# power.net
KiCad netlist of a schematic drawn in Altium Designer
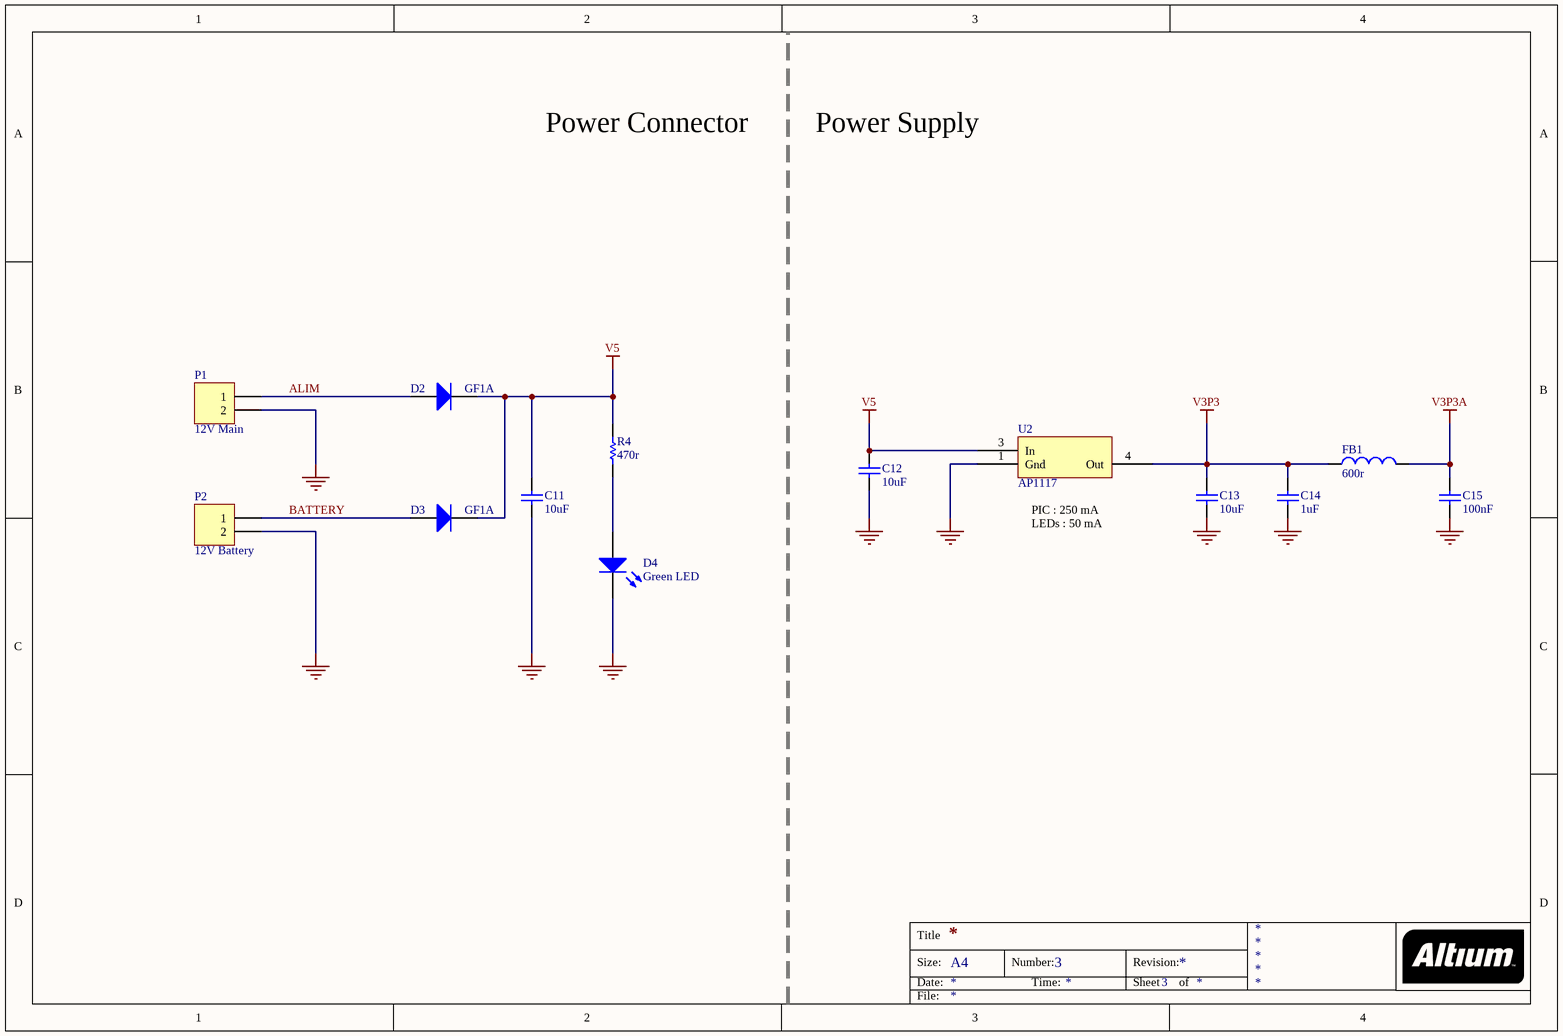
[diagram p0: power.SchDoc]

(export (version "E")
  (design (tool "Eeschema 10.0.6"))
  (components
    (comp (ref "C11")
      (value "10uF")
      (footprint "CAPC2012N")
      (description "Capacitor")
      (fields (field (name "PUBLISHER") "Altium Limited"))
      (libsource (lib "Miscellaneous Devices") (part "Cap"))
    )
    (comp (ref "C12")
      (value "10uF")
      (footprint "CAPC2012N")
      (description "Capacitor")
      (fields (field (name "PUBLISHER") "Altium Limited"))
      (libsource (lib "Miscellaneous Devices") (part "Cap"))
    )
    (comp (ref "C13")
      (value "10uF")
      (footprint "CAPC2012N")
      (description "Capacitor")
      (fields (field (name "PUBLISHER") "Altium Limited"))
      (libsource (lib "Miscellaneous Devices") (part "Cap"))
    )
    (comp (ref "C14")
      (value "1uF")
      (footprint "CAPC1608N")
      (description "Capacitor")
      (fields (field (name "PUBLISHER") "Altium Limited"))
      (libsource (lib "Miscellaneous Devices") (part "Cap"))
    )
    (comp (ref "C15")
      (value "100nF")
      (footprint "CAPC1608N")
      (description "Capacitor")
      (fields (field (name "PUBLISHER") "Altium Limited"))
      (libsource (lib "Miscellaneous Devices") (part "Cap"))
    )
    (comp (ref "D2")
      (value "GF1A")
      (footprint "SMA/DO-214AC_21")
      (description "Default Diode")
      (fields (field (name "PUBLISHER") "Altium Limited"))
      (libsource (lib "Miscellaneous Devices") (part "Diode"))
    )
    (comp (ref "D3")
      (value "GF1A")
      (footprint "SMA/DO-214AC_21")
      (description "Default Diode")
      (fields (field (name "PUBLISHER") "Altium Limited"))
      (libsource (lib "Miscellaneous Devices") (part "Diode"))
    )
    (comp (ref "D4")
      (value "Green LED")
      (footprint "LED 0805")
      (description "Typical INFRARED GaAs LED")
      (fields (field (name "PUBLISHER") "Altium Limited"))
      (libsource (lib "Miscellaneous Devices") (part "LED2"))
    )
    (comp (ref "FB1")
      (value "600r")
      (footprint "INDC1608AN")
      (description "Inductor")
      (fields (field (name "PUBLISHER") "Altium Limited"))
      (libsource (lib "Miscellaneous Devices") (part "Inductor"))
    )
    (comp (ref "P1")
      (value "12V Main")
      (footprint "PHOENIX_1985195")
      (description "Header, 2-Pin")
      (fields (field (name "PUBLISHER") "Altium Limited"))
      (libsource (lib "Miscellaneous Connectors") (part "Header 2"))
    )
    (comp (ref "P2")
      (value "12V Battery")
      (footprint "PHOENIX_1985195")
      (description "Header, 2-Pin")
      (fields (field (name "PUBLISHER") "Altium Limited"))
      (libsource (lib "Miscellaneous Connectors") (part "Header 2"))
    )
    (comp (ref "R4")
      (value "470r")
      (footprint "RESC1608N")
      (description "Resistor")
      (fields (field (name "PUBLISHER") "Altium Limited"))
      (libsource (lib "Miscellaneous Devices") (part "Res1"))
    )
    (comp (ref "U2") (value "AP1117") (footprint "TD03B_N") (libsource (lib "TP02_SCHLib") (part "AP1117")))
  )
  (nets
    (net (code "1") (name "/ALIM") (class "Default")
      (node (ref "D2") (pin "1") (pinfunction "A_1") (pintype "passive"))
      (node (ref "P1") (pin "1") (pinfunction "1_1") (pintype "passive"))
    )
    (net (code "2") (name "/BATTERY") (class "Default")
      (node (ref "D3") (pin "1") (pinfunction "A_1") (pintype "passive"))
      (node (ref "P2") (pin "1") (pinfunction "1_1") (pintype "passive"))
    )
    (net (code "3") (name "GND") (class "Default")
      (node (ref "C11") (pin "1") (pinfunction "1_1") (pintype "passive"))
      (node (ref "C12") (pin "1") (pinfunction "1_1") (pintype "passive"))
      (node (ref "C13") (pin "1") (pinfunction "1_1") (pintype "passive"))
      (node (ref "C14") (pin "1") (pinfunction "1_1") (pintype "passive"))
      (node (ref "C15") (pin "1") (pinfunction "1_1") (pintype "passive"))
      (node (ref "D4") (pin "2") (pinfunction "K_2") (pintype "passive"))
      (node (ref "P1") (pin "2") (pinfunction "2_2") (pintype "passive"))
      (node (ref "P2") (pin "2") (pinfunction "2_2") (pintype "passive"))
      (node (ref "U2") (pin "1") (pinfunction "Gnd_1") (pintype "power_in"))
    )
    (net (code "4") (name "Net-(D4-A)") (class "Default")
      (node (ref "D4") (pin "1") (pinfunction "A_1") (pintype "passive"))
      (node (ref "R4") (pin "1") (pinfunction "1_1") (pintype "passive"))
    )
    (net (code "5") (name "V3P3") (class "Default")
      (node (ref "C13") (pin "2") (pinfunction "2_2") (pintype "passive"))
      (node (ref "C14") (pin "2") (pinfunction "2_2") (pintype "passive"))
      (node (ref "FB1") (pin "1") (pinfunction "1_1") (pintype "passive"))
      (node (ref "U2") (pin "4") (pinfunction "Out_4") (pintype "power_in"))
    )
    (net (code "6") (name "V3P3A") (class "Default")
      (node (ref "C15") (pin "2") (pinfunction "2_2") (pintype "passive"))
      (node (ref "FB1") (pin "2") (pinfunction "2_2") (pintype "passive"))
    )
    (net (code "7") (name "V5") (class "Default")
      (node (ref "C11") (pin "2") (pinfunction "2_2") (pintype "passive"))
      (node (ref "C12") (pin "2") (pinfunction "2_2") (pintype "passive"))
      (node (ref "D2") (pin "2") (pinfunction "K_2") (pintype "passive"))
      (node (ref "D3") (pin "2") (pinfunction "K_2") (pintype "passive"))
      (node (ref "R4") (pin "2") (pinfunction "2_2") (pintype "passive"))
      (node (ref "U2") (pin "3") (pinfunction "In_3") (pintype "power_in"))
    )
  )
)
